# Switch.net
KiCad netlist of a schematic drawn in EAGLE
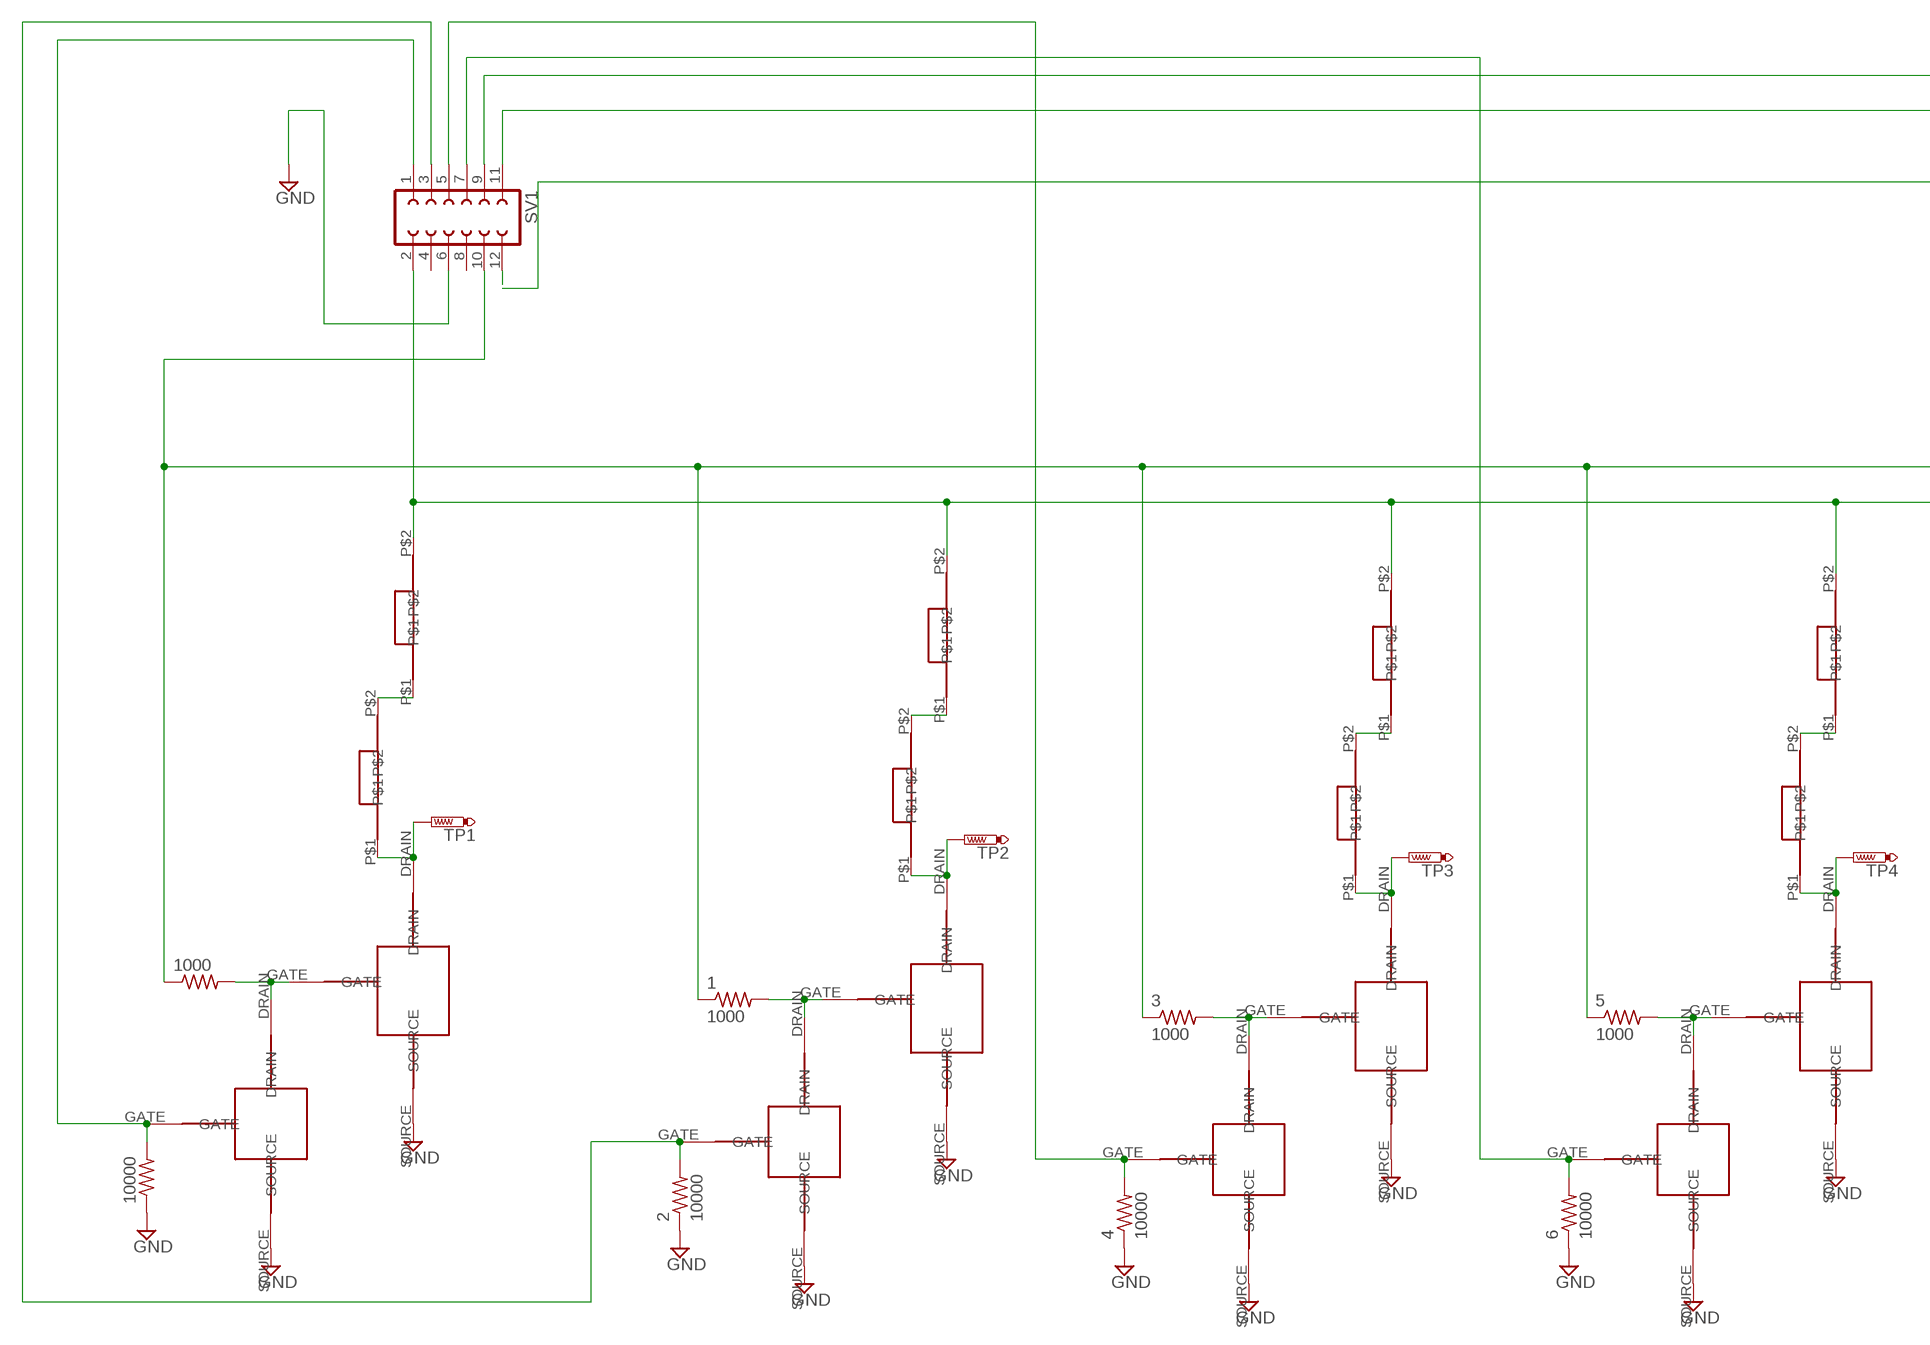
[diagram p0: schematic, sheet 1, part 1 of 2]
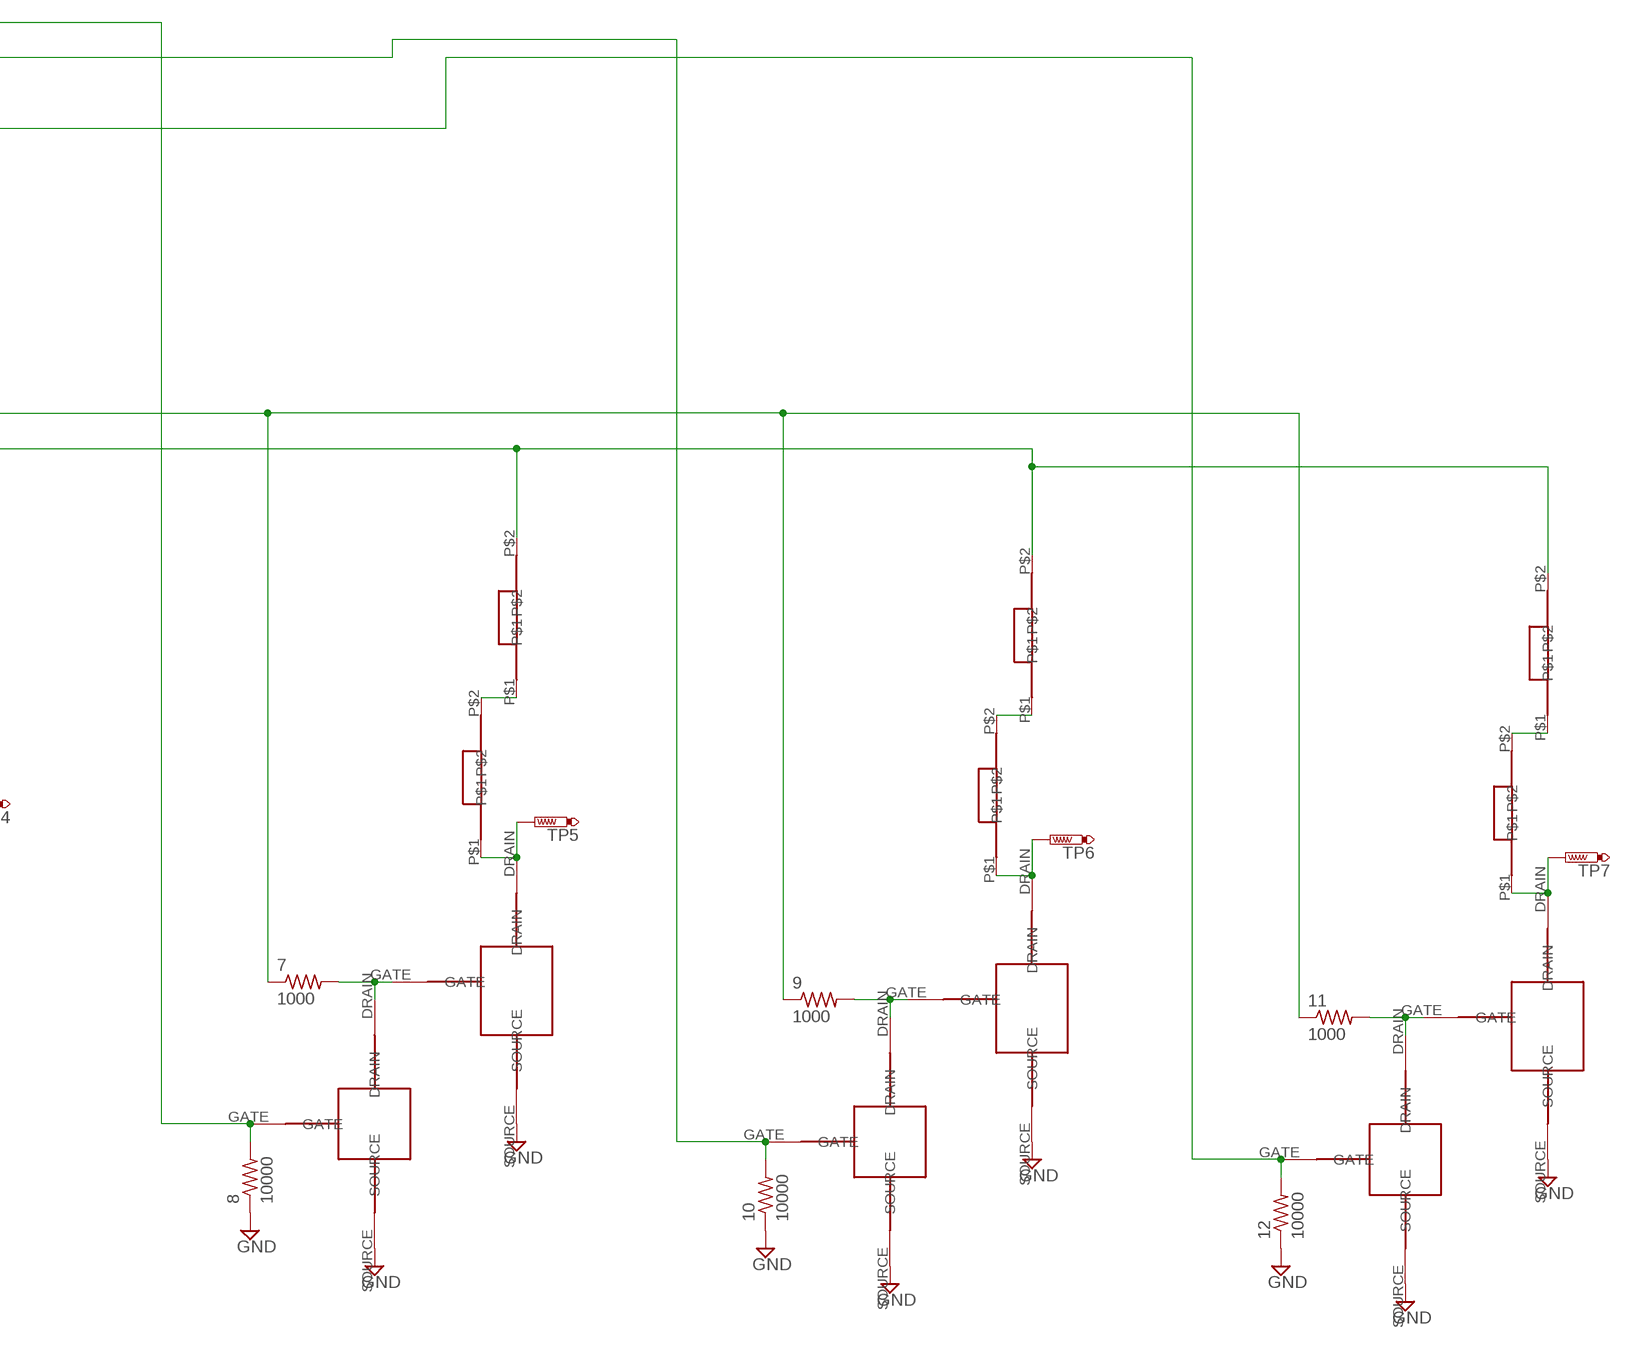
[diagram p1: schematic, sheet 1, part 2 of 2]

(export (version "E")
  (design (tool "Eeschema 10.0.6"))
  (components
    (comp (ref "1")
      (value "1000")
      (footprint "eagle-import:R0805")
      (libsource (lib "eagle-import") (part "R-US_R0805"))
    )
    (comp (ref "2")
      (value "10000")
      (footprint "eagle-import:R0805")
      (libsource (lib "eagle-import") (part "R-US_R0805"))
    )
    (comp (ref "3")
      (value "1000")
      (footprint "eagle-import:R0805")
      (libsource (lib "eagle-import") (part "R-US_R0805"))
    )
    (comp (ref "4")
      (value "10000")
      (footprint "eagle-import:R0805")
      (libsource (lib "eagle-import") (part "R-US_R0805"))
    )
    (comp (ref "5")
      (value "1000")
      (footprint "eagle-import:R0805")
      (libsource (lib "eagle-import") (part "R-US_R0805"))
    )
    (comp (ref "6")
      (value "10000")
      (footprint "eagle-import:R0805")
      (libsource (lib "eagle-import") (part "R-US_R0805"))
    )
    (comp (ref "7")
      (value "1000")
      (footprint "eagle-import:R0805")
      (libsource (lib "eagle-import") (part "R-US_R0805"))
    )
    (comp (ref "8")
      (value "10000")
      (footprint "eagle-import:R0805")
      (libsource (lib "eagle-import") (part "R-US_R0805"))
    )
    (comp (ref "9")
      (value "1000")
      (footprint "eagle-import:R0805")
      (libsource (lib "eagle-import") (part "R-US_R0805"))
    )
    (comp (ref "10")
      (value "10000")
      (footprint "eagle-import:R0805")
      (libsource (lib "eagle-import") (part "R-US_R0805"))
    )
    (comp (ref "11")
      (value "1000")
      (footprint "eagle-import:R0805")
      (libsource (lib "eagle-import") (part "R-US_R0805"))
    )
    (comp (ref "12")
      (value "10000")
      (footprint "eagle-import:R0805")
      (libsource (lib "eagle-import") (part "R-US_R0805"))
    )
    (comp (ref "1000")
      (value "R-US_R0805")
      (footprint "eagle-import:R0805")
      (libsource (lib "eagle-import") (part "R-US_R0805"))
    )
    (comp (ref "10000")
      (value "R-US_R0805")
      (footprint "eagle-import:R0805")
      (libsource (lib "eagle-import") (part "R-US_R0805"))
    )
    (comp (ref "SV1")
      (value "FE06-2")
      (footprint "eagle-import:FE06-2")
      (libsource (lib "eagle-import") (part "FE06-2"))
    )
    (comp (ref "TP1")
      (value "PTR1PAD1-13Y")
      (footprint "eagle-import:P1-13Y")
      (libsource (lib "eagle-import") (part "PTR1PAD1-13Y"))
    )
    (comp (ref "TP2")
      (value "PTR1PAD1-13Y")
      (footprint "eagle-import:P1-13Y")
      (libsource (lib "eagle-import") (part "PTR1PAD1-13Y"))
    )
    (comp (ref "TP3")
      (value "PTR1PAD1-13Y")
      (footprint "eagle-import:P1-13Y")
      (libsource (lib "eagle-import") (part "PTR1PAD1-13Y"))
    )
    (comp (ref "TP4")
      (value "PTR1PAD1-13Y")
      (footprint "eagle-import:P1-13Y")
      (libsource (lib "eagle-import") (part "PTR1PAD1-13Y"))
    )
    (comp (ref "TP5")
      (value "PTR1PAD1-13Y")
      (footprint "eagle-import:P1-13Y")
      (libsource (lib "eagle-import") (part "PTR1PAD1-13Y"))
    )
    (comp (ref "TP6")
      (value "PTR1PAD1-13Y")
      (footprint "eagle-import:P1-13Y")
      (libsource (lib "eagle-import") (part "PTR1PAD1-13Y"))
    )
    (comp (ref "TP7")
      (value "PTR1PAD1-13Y")
      (footprint "eagle-import:P1-13Y")
      (libsource (lib "eagle-import") (part "PTR1PAD1-13Y"))
    )
    (comp (ref "U$1")
      (value "FQD2N100")
      (footprint "eagle-import:DPAK")
      (libsource (lib "eagle-import") (part "FQD2N100"))
    )
    (comp (ref "U$2")
      (value "2N7000")
      (footprint "eagle-import:TO-92-AMMO")
      (libsource (lib "eagle-import") (part "2N7000"))
    )
    (comp (ref "U$3")
      (value "FQD2N100")
      (footprint "eagle-import:DPAK")
      (libsource (lib "eagle-import") (part "FQD2N100"))
    )
    (comp (ref "U$4")
      (value "2N7000")
      (footprint "eagle-import:TO-92-AMMO")
      (libsource (lib "eagle-import") (part "2N7000"))
    )
    (comp (ref "U$5")
      (value "SMD_POWER")
      (footprint "eagle-import:SMD_POWER")
      (libsource (lib "eagle-import") (part "SMD_POWER"))
    )
    (comp (ref "U$6")
      (value "SMD_POWER")
      (footprint "eagle-import:SMD_POWER")
      (libsource (lib "eagle-import") (part "SMD_POWER"))
    )
    (comp (ref "U$7")
      (value "SMD_POWER")
      (footprint "eagle-import:SMD_POWER")
      (libsource (lib "eagle-import") (part "SMD_POWER"))
    )
    (comp (ref "U$8")
      (value "SMD_POWER")
      (footprint "eagle-import:SMD_POWER")
      (libsource (lib "eagle-import") (part "SMD_POWER"))
    )
    (comp (ref "U$9")
      (value "FQD2N100")
      (footprint "eagle-import:DPAK")
      (libsource (lib "eagle-import") (part "FQD2N100"))
    )
    (comp (ref "U$10")
      (value "2N7000")
      (footprint "eagle-import:TO-92-AMMO")
      (libsource (lib "eagle-import") (part "2N7000"))
    )
    (comp (ref "U$11")
      (value "SMD_POWER")
      (footprint "eagle-import:SMD_POWER")
      (libsource (lib "eagle-import") (part "SMD_POWER"))
    )
    (comp (ref "U$12")
      (value "SMD_POWER")
      (footprint "eagle-import:SMD_POWER")
      (libsource (lib "eagle-import") (part "SMD_POWER"))
    )
    (comp (ref "U$13")
      (value "FQD2N100")
      (footprint "eagle-import:DPAK")
      (libsource (lib "eagle-import") (part "FQD2N100"))
    )
    (comp (ref "U$14")
      (value "2N7000")
      (footprint "eagle-import:TO-92-AMMO")
      (libsource (lib "eagle-import") (part "2N7000"))
    )
    (comp (ref "U$15")
      (value "SMD_POWER")
      (footprint "eagle-import:SMD_POWER")
      (libsource (lib "eagle-import") (part "SMD_POWER"))
    )
    (comp (ref "U$16")
      (value "SMD_POWER")
      (footprint "eagle-import:SMD_POWER")
      (libsource (lib "eagle-import") (part "SMD_POWER"))
    )
    (comp (ref "U$17")
      (value "FQD2N100")
      (footprint "eagle-import:DPAK")
      (libsource (lib "eagle-import") (part "FQD2N100"))
    )
    (comp (ref "U$18")
      (value "2N7000")
      (footprint "eagle-import:TO-92-AMMO")
      (libsource (lib "eagle-import") (part "2N7000"))
    )
    (comp (ref "U$19")
      (value "SMD_POWER")
      (footprint "eagle-import:SMD_POWER")
      (libsource (lib "eagle-import") (part "SMD_POWER"))
    )
    (comp (ref "U$20")
      (value "SMD_POWER")
      (footprint "eagle-import:SMD_POWER")
      (libsource (lib "eagle-import") (part "SMD_POWER"))
    )
    (comp (ref "U$21")
      (value "FQD2N100")
      (footprint "eagle-import:DPAK")
      (libsource (lib "eagle-import") (part "FQD2N100"))
    )
    (comp (ref "U$22")
      (value "2N7000")
      (footprint "eagle-import:TO-92-AMMO")
      (libsource (lib "eagle-import") (part "2N7000"))
    )
    (comp (ref "U$23")
      (value "SMD_POWER")
      (footprint "eagle-import:SMD_POWER")
      (libsource (lib "eagle-import") (part "SMD_POWER"))
    )
    (comp (ref "U$24")
      (value "SMD_POWER")
      (footprint "eagle-import:SMD_POWER")
      (libsource (lib "eagle-import") (part "SMD_POWER"))
    )
    (comp (ref "U$25")
      (value "FQD2N100")
      (footprint "eagle-import:DPAK")
      (libsource (lib "eagle-import") (part "FQD2N100"))
    )
    (comp (ref "U$26")
      (value "2N7000")
      (footprint "eagle-import:TO-92-AMMO")
      (libsource (lib "eagle-import") (part "2N7000"))
    )
    (comp (ref "U$27")
      (value "SMD_POWER")
      (footprint "eagle-import:SMD_POWER")
      (libsource (lib "eagle-import") (part "SMD_POWER"))
    )
    (comp (ref "U$28")
      (value "SMD_POWER")
      (footprint "eagle-import:SMD_POWER")
      (libsource (lib "eagle-import") (part "SMD_POWER"))
    )
  )
  (nets
    (net (code "1") (name "GND") (class "Default")
      (node (ref "10") (pin "1") (pinfunction "1_1") (pintype "passive"))
      (node (ref "10000") (pin "1") (pinfunction "1_1") (pintype "passive"))
      (node (ref "12") (pin "1") (pinfunction "1_1") (pintype "passive"))
      (node (ref "2") (pin "1") (pinfunction "1_1") (pintype "passive"))
      (node (ref "4") (pin "1") (pinfunction "1_1") (pintype "passive"))
      (node (ref "6") (pin "1") (pinfunction "1_1") (pintype "passive"))
      (node (ref "8") (pin "1") (pinfunction "1_1") (pintype "passive"))
      (node (ref "SV1") (pin "6") (pinfunction "6_6") (pintype "passive"))
      (node (ref "U$1") (pin "SOURCE") (pinfunction "SOURCE_SOURCE") (pintype "bidirectional"))
      (node (ref "U$10") (pin "SOURCE") (pinfunction "SOURCE_SOURCE") (pintype "bidirectional"))
      (node (ref "U$13") (pin "SOURCE") (pinfunction "SOURCE_SOURCE") (pintype "bidirectional"))
      (node (ref "U$14") (pin "SOURCE") (pinfunction "SOURCE_SOURCE") (pintype "bidirectional"))
      (node (ref "U$17") (pin "SOURCE") (pinfunction "SOURCE_SOURCE") (pintype "bidirectional"))
      (node (ref "U$18") (pin "SOURCE") (pinfunction "SOURCE_SOURCE") (pintype "bidirectional"))
      (node (ref "U$2") (pin "SOURCE") (pinfunction "SOURCE_SOURCE") (pintype "bidirectional"))
      (node (ref "U$21") (pin "SOURCE") (pinfunction "SOURCE_SOURCE") (pintype "bidirectional"))
      (node (ref "U$22") (pin "SOURCE") (pinfunction "SOURCE_SOURCE") (pintype "bidirectional"))
      (node (ref "U$25") (pin "SOURCE") (pinfunction "SOURCE_SOURCE") (pintype "bidirectional"))
      (node (ref "U$26") (pin "SOURCE") (pinfunction "SOURCE_SOURCE") (pintype "bidirectional"))
      (node (ref "U$3") (pin "SOURCE") (pinfunction "SOURCE_SOURCE") (pintype "bidirectional"))
      (node (ref "U$4") (pin "SOURCE") (pinfunction "SOURCE_SOURCE") (pintype "bidirectional"))
      (node (ref "U$9") (pin "SOURCE") (pinfunction "SOURCE_SOURCE") (pintype "bidirectional"))
    )
    (net (code "2") (name "Net-(1-Pad1)") (class "Default")
      (node (ref "1") (pin "1") (pinfunction "1_1") (pintype "passive"))
      (node (ref "1000") (pin "1") (pinfunction "1_1") (pintype "passive"))
      (node (ref "11") (pin "1") (pinfunction "1_1") (pintype "passive"))
      (node (ref "3") (pin "1") (pinfunction "1_1") (pintype "passive"))
      (node (ref "5") (pin "1") (pinfunction "1_1") (pintype "passive"))
      (node (ref "7") (pin "1") (pinfunction "1_1") (pintype "passive"))
      (node (ref "9") (pin "1") (pinfunction "1_1") (pintype "passive"))
      (node (ref "SV1") (pin "10") (pinfunction "10_10") (pintype "passive"))
    )
    (net (code "3") (name "Net-(1-Pad2)") (class "Default")
      (node (ref "1") (pin "2") (pinfunction "2_2") (pintype "passive"))
      (node (ref "U$3") (pin "GATE") (pinfunction "GATE_GATE") (pintype "bidirectional"))
      (node (ref "U$4") (pin "DRAIN") (pinfunction "DRAIN_DRAIN") (pintype "bidirectional"))
    )
    (net (code "4") (name "Net-(2-Pad2)") (class "Default")
      (node (ref "2") (pin "2") (pinfunction "2_2") (pintype "passive"))
      (node (ref "SV1") (pin "3") (pinfunction "3_3") (pintype "passive"))
      (node (ref "U$4") (pin "GATE") (pinfunction "GATE_GATE") (pintype "bidirectional"))
    )
    (net (code "5") (name "Net-(3-Pad2)") (class "Default")
      (node (ref "3") (pin "2") (pinfunction "2_2") (pintype "passive"))
      (node (ref "U$10") (pin "DRAIN") (pinfunction "DRAIN_DRAIN") (pintype "bidirectional"))
      (node (ref "U$9") (pin "GATE") (pinfunction "GATE_GATE") (pintype "bidirectional"))
    )
    (net (code "6") (name "Net-(4-Pad2)") (class "Default")
      (node (ref "4") (pin "2") (pinfunction "2_2") (pintype "passive"))
      (node (ref "SV1") (pin "5") (pinfunction "5_5") (pintype "passive"))
      (node (ref "U$10") (pin "GATE") (pinfunction "GATE_GATE") (pintype "bidirectional"))
    )
    (net (code "7") (name "Net-(5-Pad2)") (class "Default")
      (node (ref "5") (pin "2") (pinfunction "2_2") (pintype "passive"))
      (node (ref "U$13") (pin "GATE") (pinfunction "GATE_GATE") (pintype "bidirectional"))
      (node (ref "U$14") (pin "DRAIN") (pinfunction "DRAIN_DRAIN") (pintype "bidirectional"))
    )
    (net (code "8") (name "Net-(6-Pad2)") (class "Default")
      (node (ref "6") (pin "2") (pinfunction "2_2") (pintype "passive"))
      (node (ref "SV1") (pin "7") (pinfunction "7_7") (pintype "passive"))
      (node (ref "U$14") (pin "GATE") (pinfunction "GATE_GATE") (pintype "bidirectional"))
    )
    (net (code "9") (name "Net-(7-Pad2)") (class "Default")
      (node (ref "7") (pin "2") (pinfunction "2_2") (pintype "passive"))
      (node (ref "U$17") (pin "GATE") (pinfunction "GATE_GATE") (pintype "bidirectional"))
      (node (ref "U$18") (pin "DRAIN") (pinfunction "DRAIN_DRAIN") (pintype "bidirectional"))
    )
    (net (code "10") (name "Net-(8-Pad2)") (class "Default")
      (node (ref "8") (pin "2") (pinfunction "2_2") (pintype "passive"))
      (node (ref "SV1") (pin "9") (pinfunction "9_9") (pintype "passive"))
      (node (ref "U$18") (pin "GATE") (pinfunction "GATE_GATE") (pintype "bidirectional"))
    )
    (net (code "11") (name "Net-(9-Pad2)") (class "Default")
      (node (ref "9") (pin "2") (pinfunction "2_2") (pintype "passive"))
      (node (ref "U$21") (pin "GATE") (pinfunction "GATE_GATE") (pintype "bidirectional"))
      (node (ref "U$22") (pin "DRAIN") (pinfunction "DRAIN_DRAIN") (pintype "bidirectional"))
    )
    (net (code "12") (name "Net-(10-Pad2)") (class "Default")
      (node (ref "10") (pin "2") (pinfunction "2_2") (pintype "passive"))
      (node (ref "SV1") (pin "11") (pinfunction "11_11") (pintype "passive"))
      (node (ref "U$22") (pin "GATE") (pinfunction "GATE_GATE") (pintype "bidirectional"))
    )
    (net (code "13") (name "Net-(11-Pad2)") (class "Default")
      (node (ref "11") (pin "2") (pinfunction "2_2") (pintype "passive"))
      (node (ref "U$25") (pin "GATE") (pinfunction "GATE_GATE") (pintype "bidirectional"))
      (node (ref "U$26") (pin "DRAIN") (pinfunction "DRAIN_DRAIN") (pintype "bidirectional"))
    )
    (net (code "14") (name "Net-(12-Pad2)") (class "Default")
      (node (ref "12") (pin "2") (pinfunction "2_2") (pintype "passive"))
      (node (ref "SV1") (pin "12") (pinfunction "12_12") (pintype "passive"))
      (node (ref "U$26") (pin "GATE") (pinfunction "GATE_GATE") (pintype "bidirectional"))
    )
    (net (code "15") (name "Net-(1000-Pad2)") (class "Default")
      (node (ref "1000") (pin "2") (pinfunction "2_2") (pintype "passive"))
      (node (ref "U$1") (pin "GATE") (pinfunction "GATE_GATE") (pintype "bidirectional"))
      (node (ref "U$2") (pin "DRAIN") (pinfunction "DRAIN_DRAIN") (pintype "bidirectional"))
    )
    (net (code "16") (name "Net-(10000-Pad2)") (class "Default")
      (node (ref "10000") (pin "2") (pinfunction "2_2") (pintype "passive"))
      (node (ref "SV1") (pin "1") (pinfunction "1_1") (pintype "passive"))
      (node (ref "U$2") (pin "GATE") (pinfunction "GATE_GATE") (pintype "bidirectional"))
    )
    (net (code "17") (name "Net-(SV1-Pad2)") (class "Default")
      (node (ref "SV1") (pin "2") (pinfunction "2_2") (pintype "passive"))
      (node (ref "U$12") (pin "P$2") (pinfunction "P$2_P$2") (pintype "bidirectional"))
      (node (ref "U$16") (pin "P$2") (pinfunction "P$2_P$2") (pintype "bidirectional"))
      (node (ref "U$20") (pin "P$2") (pinfunction "P$2_P$2") (pintype "bidirectional"))
      (node (ref "U$24") (pin "P$2") (pinfunction "P$2_P$2") (pintype "bidirectional"))
      (node (ref "U$28") (pin "P$2") (pinfunction "P$2_P$2") (pintype "bidirectional"))
      (node (ref "U$6") (pin "P$2") (pinfunction "P$2_P$2") (pintype "bidirectional"))
      (node (ref "U$8") (pin "P$2") (pinfunction "P$2_P$2") (pintype "bidirectional"))
    )
    (net (code "18") (name "Net-(TP1-PadTP)") (class "Default")
      (node (ref "TP1") (pin "TP") (pinfunction "TP_TP") (pintype "input"))
      (node (ref "U$1") (pin "DRAIN") (pinfunction "DRAIN_DRAIN") (pintype "bidirectional"))
      (node (ref "U$5") (pin "P$1") (pinfunction "P$1_P$1") (pintype "bidirectional"))
    )
    (net (code "19") (name "Net-(TP2-PadTP)") (class "Default")
      (node (ref "TP2") (pin "TP") (pinfunction "TP_TP") (pintype "input"))
      (node (ref "U$3") (pin "DRAIN") (pinfunction "DRAIN_DRAIN") (pintype "bidirectional"))
      (node (ref "U$7") (pin "P$1") (pinfunction "P$1_P$1") (pintype "bidirectional"))
    )
    (net (code "20") (name "Net-(TP3-PadTP)") (class "Default")
      (node (ref "TP3") (pin "TP") (pinfunction "TP_TP") (pintype "input"))
      (node (ref "U$11") (pin "P$1") (pinfunction "P$1_P$1") (pintype "bidirectional"))
      (node (ref "U$9") (pin "DRAIN") (pinfunction "DRAIN_DRAIN") (pintype "bidirectional"))
    )
    (net (code "21") (name "Net-(TP4-PadTP)") (class "Default")
      (node (ref "TP4") (pin "TP") (pinfunction "TP_TP") (pintype "input"))
      (node (ref "U$13") (pin "DRAIN") (pinfunction "DRAIN_DRAIN") (pintype "bidirectional"))
      (node (ref "U$15") (pin "P$1") (pinfunction "P$1_P$1") (pintype "bidirectional"))
    )
    (net (code "22") (name "Net-(TP5-PadTP)") (class "Default")
      (node (ref "TP5") (pin "TP") (pinfunction "TP_TP") (pintype "input"))
      (node (ref "U$17") (pin "DRAIN") (pinfunction "DRAIN_DRAIN") (pintype "bidirectional"))
      (node (ref "U$19") (pin "P$1") (pinfunction "P$1_P$1") (pintype "bidirectional"))
    )
    (net (code "23") (name "Net-(TP6-PadTP)") (class "Default")
      (node (ref "TP6") (pin "TP") (pinfunction "TP_TP") (pintype "input"))
      (node (ref "U$21") (pin "DRAIN") (pinfunction "DRAIN_DRAIN") (pintype "bidirectional"))
      (node (ref "U$23") (pin "P$1") (pinfunction "P$1_P$1") (pintype "bidirectional"))
    )
    (net (code "24") (name "Net-(TP7-PadTP)") (class "Default")
      (node (ref "TP7") (pin "TP") (pinfunction "TP_TP") (pintype "input"))
      (node (ref "U$25") (pin "DRAIN") (pinfunction "DRAIN_DRAIN") (pintype "bidirectional"))
      (node (ref "U$27") (pin "P$1") (pinfunction "P$1_P$1") (pintype "bidirectional"))
    )
    (net (code "25") (name "Net-(U$5-PadP$2)") (class "Default")
      (node (ref "U$5") (pin "P$2") (pinfunction "P$2_P$2") (pintype "bidirectional"))
      (node (ref "U$6") (pin "P$1") (pinfunction "P$1_P$1") (pintype "bidirectional"))
    )
    (net (code "26") (name "Net-(U$7-PadP$2)") (class "Default")
      (node (ref "U$7") (pin "P$2") (pinfunction "P$2_P$2") (pintype "bidirectional"))
      (node (ref "U$8") (pin "P$1") (pinfunction "P$1_P$1") (pintype "bidirectional"))
    )
    (net (code "27") (name "Net-(U$11-PadP$2)") (class "Default")
      (node (ref "U$11") (pin "P$2") (pinfunction "P$2_P$2") (pintype "bidirectional"))
      (node (ref "U$12") (pin "P$1") (pinfunction "P$1_P$1") (pintype "bidirectional"))
    )
    (net (code "28") (name "Net-(U$15-PadP$2)") (class "Default")
      (node (ref "U$15") (pin "P$2") (pinfunction "P$2_P$2") (pintype "bidirectional"))
      (node (ref "U$16") (pin "P$1") (pinfunction "P$1_P$1") (pintype "bidirectional"))
    )
    (net (code "29") (name "Net-(U$19-PadP$2)") (class "Default")
      (node (ref "U$19") (pin "P$2") (pinfunction "P$2_P$2") (pintype "bidirectional"))
      (node (ref "U$20") (pin "P$1") (pinfunction "P$1_P$1") (pintype "bidirectional"))
    )
    (net (code "30") (name "Net-(U$23-PadP$2)") (class "Default")
      (node (ref "U$23") (pin "P$2") (pinfunction "P$2_P$2") (pintype "bidirectional"))
      (node (ref "U$24") (pin "P$1") (pinfunction "P$1_P$1") (pintype "bidirectional"))
    )
    (net (code "31") (name "Net-(U$27-PadP$2)") (class "Default")
      (node (ref "U$27") (pin "P$2") (pinfunction "P$2_P$2") (pintype "bidirectional"))
      (node (ref "U$28") (pin "P$1") (pinfunction "P$1_P$1") (pintype "bidirectional"))
    )
    (net (code "32") (name "unconnected-(SV1-Pad4)") (class "Default")
      (node (ref "SV1") (pin "4") (pinfunction "4_4") (pintype "passive"))
    )
    (net (code "33") (name "unconnected-(SV1-Pad8)") (class "Default")
      (node (ref "SV1") (pin "8") (pinfunction "8_8") (pintype "passive"))
    )
  )
)
